# SAW-TOOTH-DAC0808.net
KiCad netlist of a schematic drawn in Altium Designer
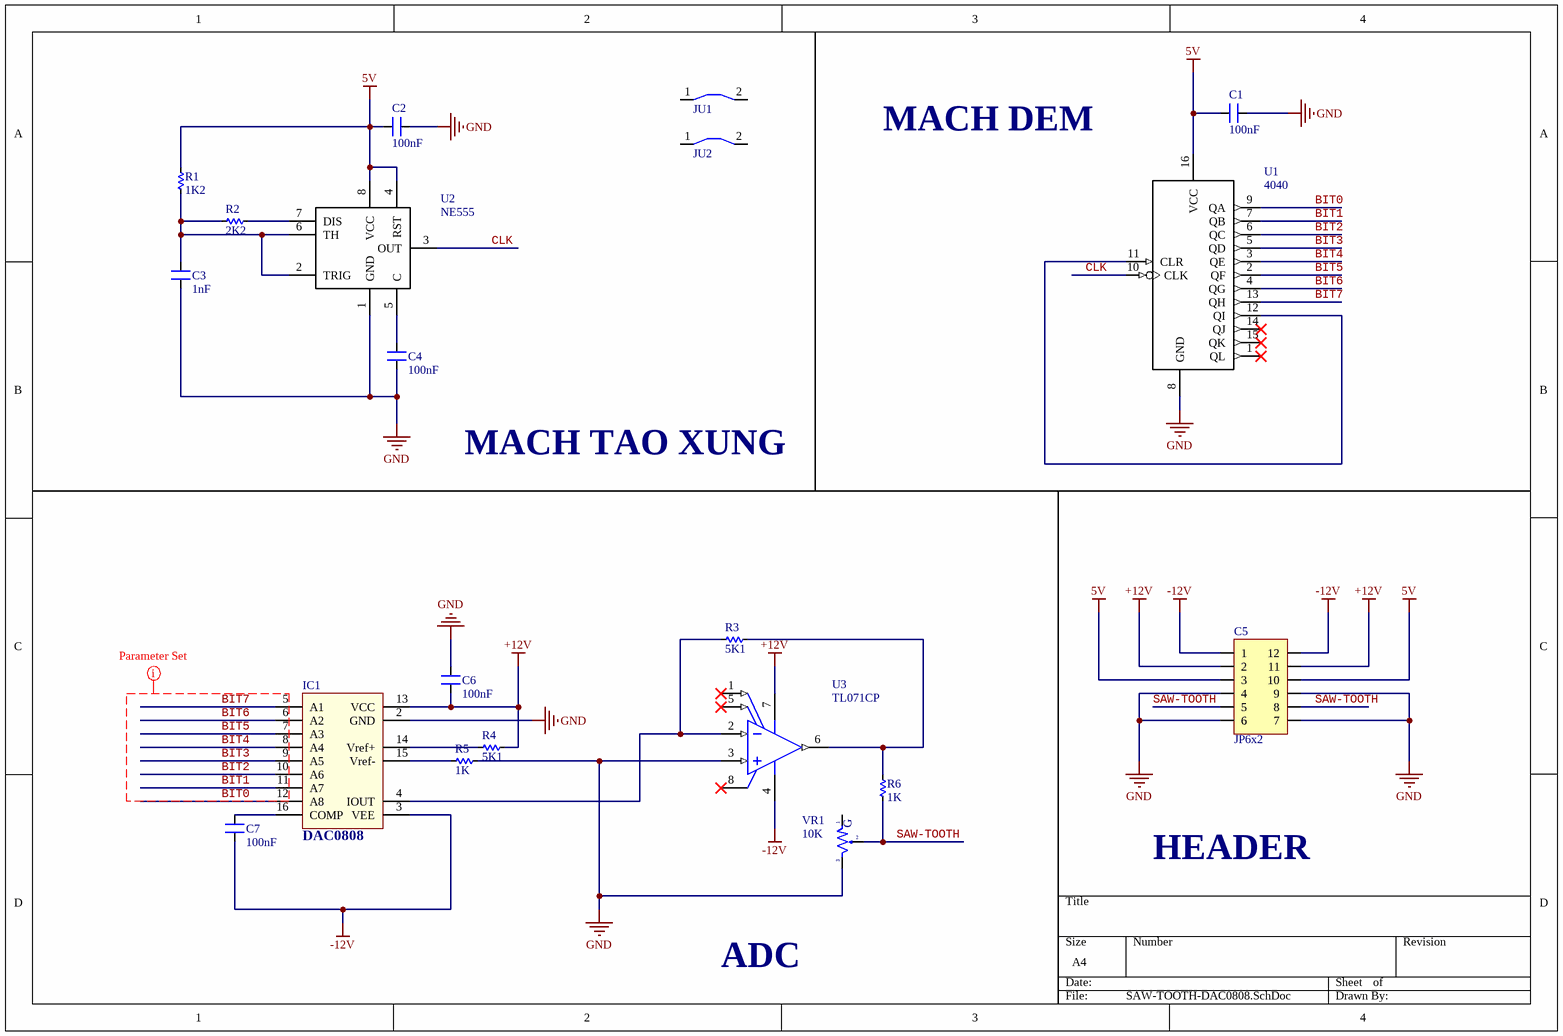
[diagram p0: SAW-TOOTH-DAC0808.SchDoc]

(export (version "E")
  (design (tool "Eeschema 10.0.6"))
  (components
    (comp (ref "C1") (value "100nF") (footprint "CN1") (libsource (lib "LIBRARY_MuaLinhKien") (part "CN")))
    (comp (ref "C2") (value "100nF") (footprint "CN1") (libsource (lib "LIBRARY_MuaLinhKien") (part "CN")))
    (comp (ref "C3") (value "1nF") (footprint "CN1") (libsource (lib "LIBRARY_MuaLinhKien") (part "CN")))
    (comp (ref "C4") (value "100nF") (footprint "CN1") (libsource (lib "LIBRARY_MuaLinhKien") (part "CN")))
    (comp (ref "C5")
      (value "JP6x2")
      (footprint "JP6-D2T")
      (description "WR-PHD 2.54 mm Dual Socket Header")
      (fields
        (field (name "MANUFACTURER") "Würth Elektronik eiSos GmbH")
        (field (name "PARTNO") "61301221821")
        (field (name "CREATED BY") "Karrer Zheng")
      )
      (libsource (lib "LIBRARY_MuaLinhKien") (part "JP6x2"))
    )
    (comp (ref "C6") (value "100nF") (footprint "CN1") (libsource (lib "LIBRARY_MuaLinhKien") (part "CN")))
    (comp (ref "C7") (value "100nF") (footprint "CN1") (libsource (lib "LIBRARY_MuaLinhKien") (part "CN")))
    (comp (ref "IC1")
      (value "DAC0808")
      (footprint "DIP16")
      (description "8 Bits Digital Analog Convert")
      (libsource (lib "LIBRARY_MuaLinhKien") (part "DAC0808"))
    )
    (comp (ref "JU1")
      (value "JUMPER 5MM")
      (footprint "JUMPER 5MM")
      (libsource (lib "tunaSchlib") (part "JUMPER 5MM"))
    )
    (comp (ref "JU2")
      (value "JUMPER 5MM")
      (footprint "JUMPER 5MM")
      (libsource (lib "tunaSchlib") (part "JUMPER 5MM"))
    )
    (comp (ref "R1")
      (value "1K2")
      (footprint "RES-1/4W")
      (description "Res")
      (fields
        (field (name "MANUFACTURER") "Generic Components")
        (field (name "PUBLISHER") "Altium Hobart Technology Centre")
      )
      (libsource (lib "LIBRARY_MuaLinhKien") (part "Res"))
    )
    (comp (ref "R2")
      (value "2K2")
      (footprint "RES-1/4W")
      (description "Res")
      (fields
        (field (name "MANUFACTURER") "Generic Components")
        (field (name "PUBLISHER") "Altium Hobart Technology Centre")
      )
      (libsource (lib "LIBRARY_MuaLinhKien") (part "Res"))
    )
    (comp (ref "R3")
      (value "5K1")
      (footprint "RES-1/4W")
      (description "Res")
      (fields
        (field (name "MANUFACTURER") "Generic Components")
        (field (name "PUBLISHER") "Altium Hobart Technology Centre")
      )
      (libsource (lib "LIBRARY_MuaLinhKien") (part "Res"))
    )
    (comp (ref "R4")
      (value "5K1")
      (footprint "RES-1/4W")
      (description "Res")
      (fields
        (field (name "MANUFACTURER") "Generic Components")
        (field (name "PUBLISHER") "Altium Hobart Technology Centre")
      )
      (libsource (lib "LIBRARY_MuaLinhKien") (part "Res"))
    )
    (comp (ref "R5")
      (value "1K")
      (footprint "RES-1/4W")
      (description "Res")
      (fields
        (field (name "MANUFACTURER") "Generic Components")
        (field (name "PUBLISHER") "Altium Hobart Technology Centre")
      )
      (libsource (lib "LIBRARY_MuaLinhKien") (part "Res"))
    )
    (comp (ref "R6")
      (value "1K")
      (footprint "RES-1/4W")
      (description "Res")
      (fields
        (field (name "MANUFACTURER") "Generic Components")
        (field (name "PUBLISHER") "Altium Hobart Technology Centre")
      )
      (libsource (lib "LIBRARY_MuaLinhKien") (part "Res"))
    )
    (comp (ref "U1")
      (value "4040")
      (footprint "DIP16")
      (description "ASYNCHRONOUS 12-BIT BINARY COUNTERS")
      (libsource (lib "LIBRARY_MuaLinhKien") (part "4040"))
    )
    (comp (ref "U2")
      (value "NE555")
      (footprint "DIP8")
      (description "TIMER IC")
      (fields
        (field (name "MANUFACTURER PART NUMBER") "NE555DT")
        (field (name "MANUFACTURER") "STMicroelectronics")
      )
      (libsource (lib "LIBRARY_MuaLinhKien") (part "NE555"))
    )
    (comp (ref "U3")
      (value "TL071CP")
      (footprint "P0008A")
      (fields (field (name "MANUFACTURER") "Texas Instruments"))
      (libsource (lib "Altium Content Vault") (part "TI-AMP-S5-2-8"))
    )
    (comp (ref "VR1")
      (value "10K")
      (footprint "VR-S1")
      (description "Var Resistor")
      (libsource (lib "LIBRARY_MuaLinhKien") (part "VR-S"))
    )
  )
  (nets
    (net (code "1") (name "+12V") (class "Default")
      (node (ref "C5") (pin "11") (pinfunction "11_11") (pintype "passive"))
      (node (ref "C5") (pin "2") (pinfunction "2_2") (pintype "passive"))
      (node (ref "C6") (pin "1") (pinfunction "1_1") (pintype "passive"))
      (node (ref "IC1") (pin "13") (pinfunction "VCC_13") (pintype "power_in"))
      (node (ref "R4") (pin "1") (pinfunction "1_1") (pintype "passive"))
      (node (ref "U3") (pin "7") (pinfunction "VCC+_7") (pintype "power_in"))
    )
    (net (code "2") (name "-12V") (class "Default")
      (node (ref "C5") (pin "1") (pinfunction "1_1") (pintype "passive"))
      (node (ref "C5") (pin "12") (pinfunction "12_12") (pintype "passive"))
      (node (ref "C7") (pin "2") (pinfunction "2_2") (pintype "passive"))
      (node (ref "IC1") (pin "3") (pinfunction "VEE_3") (pintype "passive"))
      (node (ref "U3") (pin "4") (pinfunction "VCC-_4") (pintype "power_in"))
    )
    (net (code "3") (name "/BIT0") (class "Default")
      (node (ref "IC1") (pin "12") (pinfunction "A8_12") (pintype "passive"))
      (node (ref "U1") (pin "9") (pinfunction "QA_9") (pintype "output"))
    )
    (net (code "4") (name "/BIT1") (class "Default")
      (node (ref "IC1") (pin "11") (pinfunction "A7_11") (pintype "passive"))
      (node (ref "U1") (pin "7") (pinfunction "QB_7") (pintype "output"))
    )
    (net (code "5") (name "/BIT2") (class "Default")
      (node (ref "IC1") (pin "10") (pinfunction "A6_10") (pintype "passive"))
      (node (ref "U1") (pin "6") (pinfunction "QC_6") (pintype "output"))
    )
    (net (code "6") (name "/BIT3") (class "Default")
      (node (ref "IC1") (pin "9") (pinfunction "A5_9") (pintype "passive"))
      (node (ref "U1") (pin "5") (pinfunction "QD_5") (pintype "output"))
    )
    (net (code "7") (name "/BIT4") (class "Default")
      (node (ref "IC1") (pin "8") (pinfunction "A4_8") (pintype "passive"))
      (node (ref "U1") (pin "3") (pinfunction "QE_3") (pintype "output"))
    )
    (net (code "8") (name "/BIT5") (class "Default")
      (node (ref "IC1") (pin "7") (pinfunction "A3_7") (pintype "passive"))
      (node (ref "U1") (pin "2") (pinfunction "QF_2") (pintype "output"))
    )
    (net (code "9") (name "/BIT6") (class "Default")
      (node (ref "IC1") (pin "6") (pinfunction "A2_6") (pintype "passive"))
      (node (ref "U1") (pin "4") (pinfunction "QG_4") (pintype "output"))
    )
    (net (code "10") (name "/BIT7") (class "Default")
      (node (ref "IC1") (pin "5") (pinfunction "A1_5") (pintype "passive"))
      (node (ref "U1") (pin "13") (pinfunction "QH_13") (pintype "output"))
    )
    (net (code "11") (name "/CLK") (class "Default")
      (node (ref "U1") (pin "10") (pinfunction "CLK_10") (pintype "input"))
      (node (ref "U2") (pin "3") (pinfunction "OUT_3") (pintype "passive"))
    )
    (net (code "12") (name "/SAW-TOOTH") (class "Default")
      (node (ref "C5") (pin "5") (pinfunction "5_5") (pintype "passive"))
      (node (ref "C5") (pin "8") (pinfunction "8_8") (pintype "passive"))
      (node (ref "R6") (pin "2") (pinfunction "2_2") (pintype "passive"))
      (node (ref "VR1") (pin "2") (pinfunction "2_2") (pintype "passive"))
    )
    (net (code "13") (name "5V") (class "Default")
      (node (ref "C1") (pin "2") (pinfunction "2_2") (pintype "passive"))
      (node (ref "C2") (pin "2") (pinfunction "2_2") (pintype "passive"))
      (node (ref "C5") (pin "10") (pinfunction "10_10") (pintype "passive"))
      (node (ref "C5") (pin "3") (pinfunction "3_3") (pintype "passive"))
      (node (ref "R1") (pin "1") (pinfunction "1_1") (pintype "passive"))
      (node (ref "U1") (pin "16") (pinfunction "VCC_16") (pintype "power_in"))
      (node (ref "U2") (pin "4") (pinfunction "RST_4") (pintype "passive"))
      (node (ref "U2") (pin "8") (pinfunction "VCC_8") (pintype "passive"))
    )
    (net (code "14") (name "GND") (class "Default")
      (node (ref "C1") (pin "1") (pinfunction "1_1") (pintype "passive"))
      (node (ref "C2") (pin "1") (pinfunction "1_1") (pintype "passive"))
      (node (ref "C3") (pin "2") (pinfunction "2_2") (pintype "passive"))
      (node (ref "C4") (pin "2") (pinfunction "2_2") (pintype "passive"))
      (node (ref "C5") (pin "4") (pinfunction "4_4") (pintype "passive"))
      (node (ref "C5") (pin "6") (pinfunction "6_6") (pintype "passive"))
      (node (ref "C5") (pin "7") (pinfunction "7_7") (pintype "passive"))
      (node (ref "C5") (pin "9") (pinfunction "9_9") (pintype "passive"))
      (node (ref "C6") (pin "2") (pinfunction "2_2") (pintype "passive"))
      (node (ref "IC1") (pin "2") (pinfunction "GND_2") (pintype "passive"))
      (node (ref "R5") (pin "1") (pinfunction "1_1") (pintype "passive"))
      (node (ref "U1") (pin "8") (pinfunction "GND_8") (pintype "power_in"))
      (node (ref "U2") (pin "1") (pinfunction "GND_1") (pintype "passive"))
      (node (ref "U3") (pin "3") (pinfunction "IN+_3") (pintype "input"))
      (node (ref "VR1") (pin "3") (pinfunction "3_3") (pintype "passive"))
    )
    (net (code "15") (name "Net-(IC1-COMP)") (class "Default")
      (node (ref "C7") (pin "1") (pinfunction "1_1") (pintype "passive"))
      (node (ref "IC1") (pin "16") (pinfunction "COMP_16") (pintype "passive"))
    )
    (net (code "16") (name "Net-(IC1-IOUT)") (class "Default")
      (node (ref "IC1") (pin "4") (pinfunction "IOUT_4") (pintype "passive"))
      (node (ref "R3") (pin "2") (pinfunction "2_2") (pintype "passive"))
      (node (ref "U3") (pin "2") (pinfunction "IN-_2") (pintype "input"))
    )
    (net (code "17") (name "Net-(IC1-Vref+)") (class "Default")
      (node (ref "IC1") (pin "14") (pinfunction "Vref+_14") (pintype "passive"))
      (node (ref "R4") (pin "2") (pinfunction "2_2") (pintype "passive"))
    )
    (net (code "18") (name "Net-(IC1-Vref-)") (class "Default")
      (node (ref "IC1") (pin "15") (pinfunction "Vref-_15") (pintype "passive"))
      (node (ref "R5") (pin "2") (pinfunction "2_2") (pintype "passive"))
    )
    (net (code "19") (name "Net-(U1-CLR)") (class "Default")
      (node (ref "U1") (pin "11") (pinfunction "CLR_11") (pintype "input"))
      (node (ref "U1") (pin "12") (pinfunction "QI_12") (pintype "output"))
    )
    (net (code "20") (name "Net-(U2-C)") (class "Default")
      (node (ref "C4") (pin "1") (pinfunction "1_1") (pintype "passive"))
      (node (ref "U2") (pin "5") (pinfunction "C_5") (pintype "passive"))
    )
    (net (code "21") (name "Net-(U2-DIS)") (class "Default")
      (node (ref "R2") (pin "1") (pinfunction "1_1") (pintype "passive"))
      (node (ref "U2") (pin "7") (pinfunction "DIS_7") (pintype "passive"))
    )
    (net (code "22") (name "Net-(U2-TH)") (class "Default")
      (node (ref "C3") (pin "1") (pinfunction "1_1") (pintype "passive"))
      (node (ref "R1") (pin "2") (pinfunction "2_2") (pintype "passive"))
      (node (ref "R2") (pin "2") (pinfunction "2_2") (pintype "passive"))
      (node (ref "U2") (pin "2") (pinfunction "TRIG_2") (pintype "passive"))
      (node (ref "U2") (pin "6") (pinfunction "TH_6") (pintype "passive"))
    )
    (net (code "23") (name "Net-(U3-OUT)") (class "Default")
      (node (ref "R3") (pin "1") (pinfunction "1_1") (pintype "passive"))
      (node (ref "R6") (pin "1") (pinfunction "1_1") (pintype "passive"))
      (node (ref "U3") (pin "6") (pinfunction "OUT_6") (pintype "output"))
    )
    (net (code "24") (name "unconnected-(JU1-Pad1)") (class "Default")
      (node (ref "JU1") (pin "1") (pinfunction "1_1") (pintype "power_in"))
    )
    (net (code "25") (name "unconnected-(JU1-Pad2)") (class "Default")
      (node (ref "JU1") (pin "2") (pinfunction "2_2") (pintype "power_in"))
    )
    (net (code "26") (name "unconnected-(JU2-Pad1)") (class "Default")
      (node (ref "JU2") (pin "1") (pinfunction "1_1") (pintype "power_in"))
    )
    (net (code "27") (name "unconnected-(JU2-Pad2)") (class "Default")
      (node (ref "JU2") (pin "2") (pinfunction "2_2") (pintype "power_in"))
    )
    (net (code "28") (name "unconnected-(U1-QJ-Pad14)") (class "Default")
      (node (ref "U1") (pin "14") (pinfunction "QJ_14") (pintype "output+no_connect"))
    )
    (net (code "29") (name "unconnected-(U1-QK-Pad15)") (class "Default")
      (node (ref "U1") (pin "15") (pinfunction "QK_15") (pintype "output+no_connect"))
    )
    (net (code "30") (name "unconnected-(U1-QL-Pad1)") (class "Default")
      (node (ref "U1") (pin "1") (pinfunction "QL_1") (pintype "output+no_connect"))
    )
    (net (code "31") (name "unconnected-(U3-NC-Pad8)") (class "Default")
      (node (ref "U3") (pin "8") (pinfunction "NC_8") (pintype "passive+no_connect"))
    )
    (net (code "32") (name "unconnected-(U3-OFFSET_N1-Pad1)") (class "Default")
      (node (ref "U3") (pin "1") (pinfunction "OFFSET_N1_1") (pintype "input+no_connect"))
    )
    (net (code "33") (name "unconnected-(U3-OFFSET_N2-Pad5)") (class "Default")
      (node (ref "U3") (pin "5") (pinfunction "OFFSET_N2_5") (pintype "input+no_connect"))
    )
    (net (code "34") (name "unconnected-(VR1-Pad1)") (class "Default")
      (node (ref "VR1") (pin "1") (pinfunction "1_1") (pintype "passive"))
    )
  )
)
